# MotorCell.net
KiCad netlist of a schematic drawn in Altium Designer
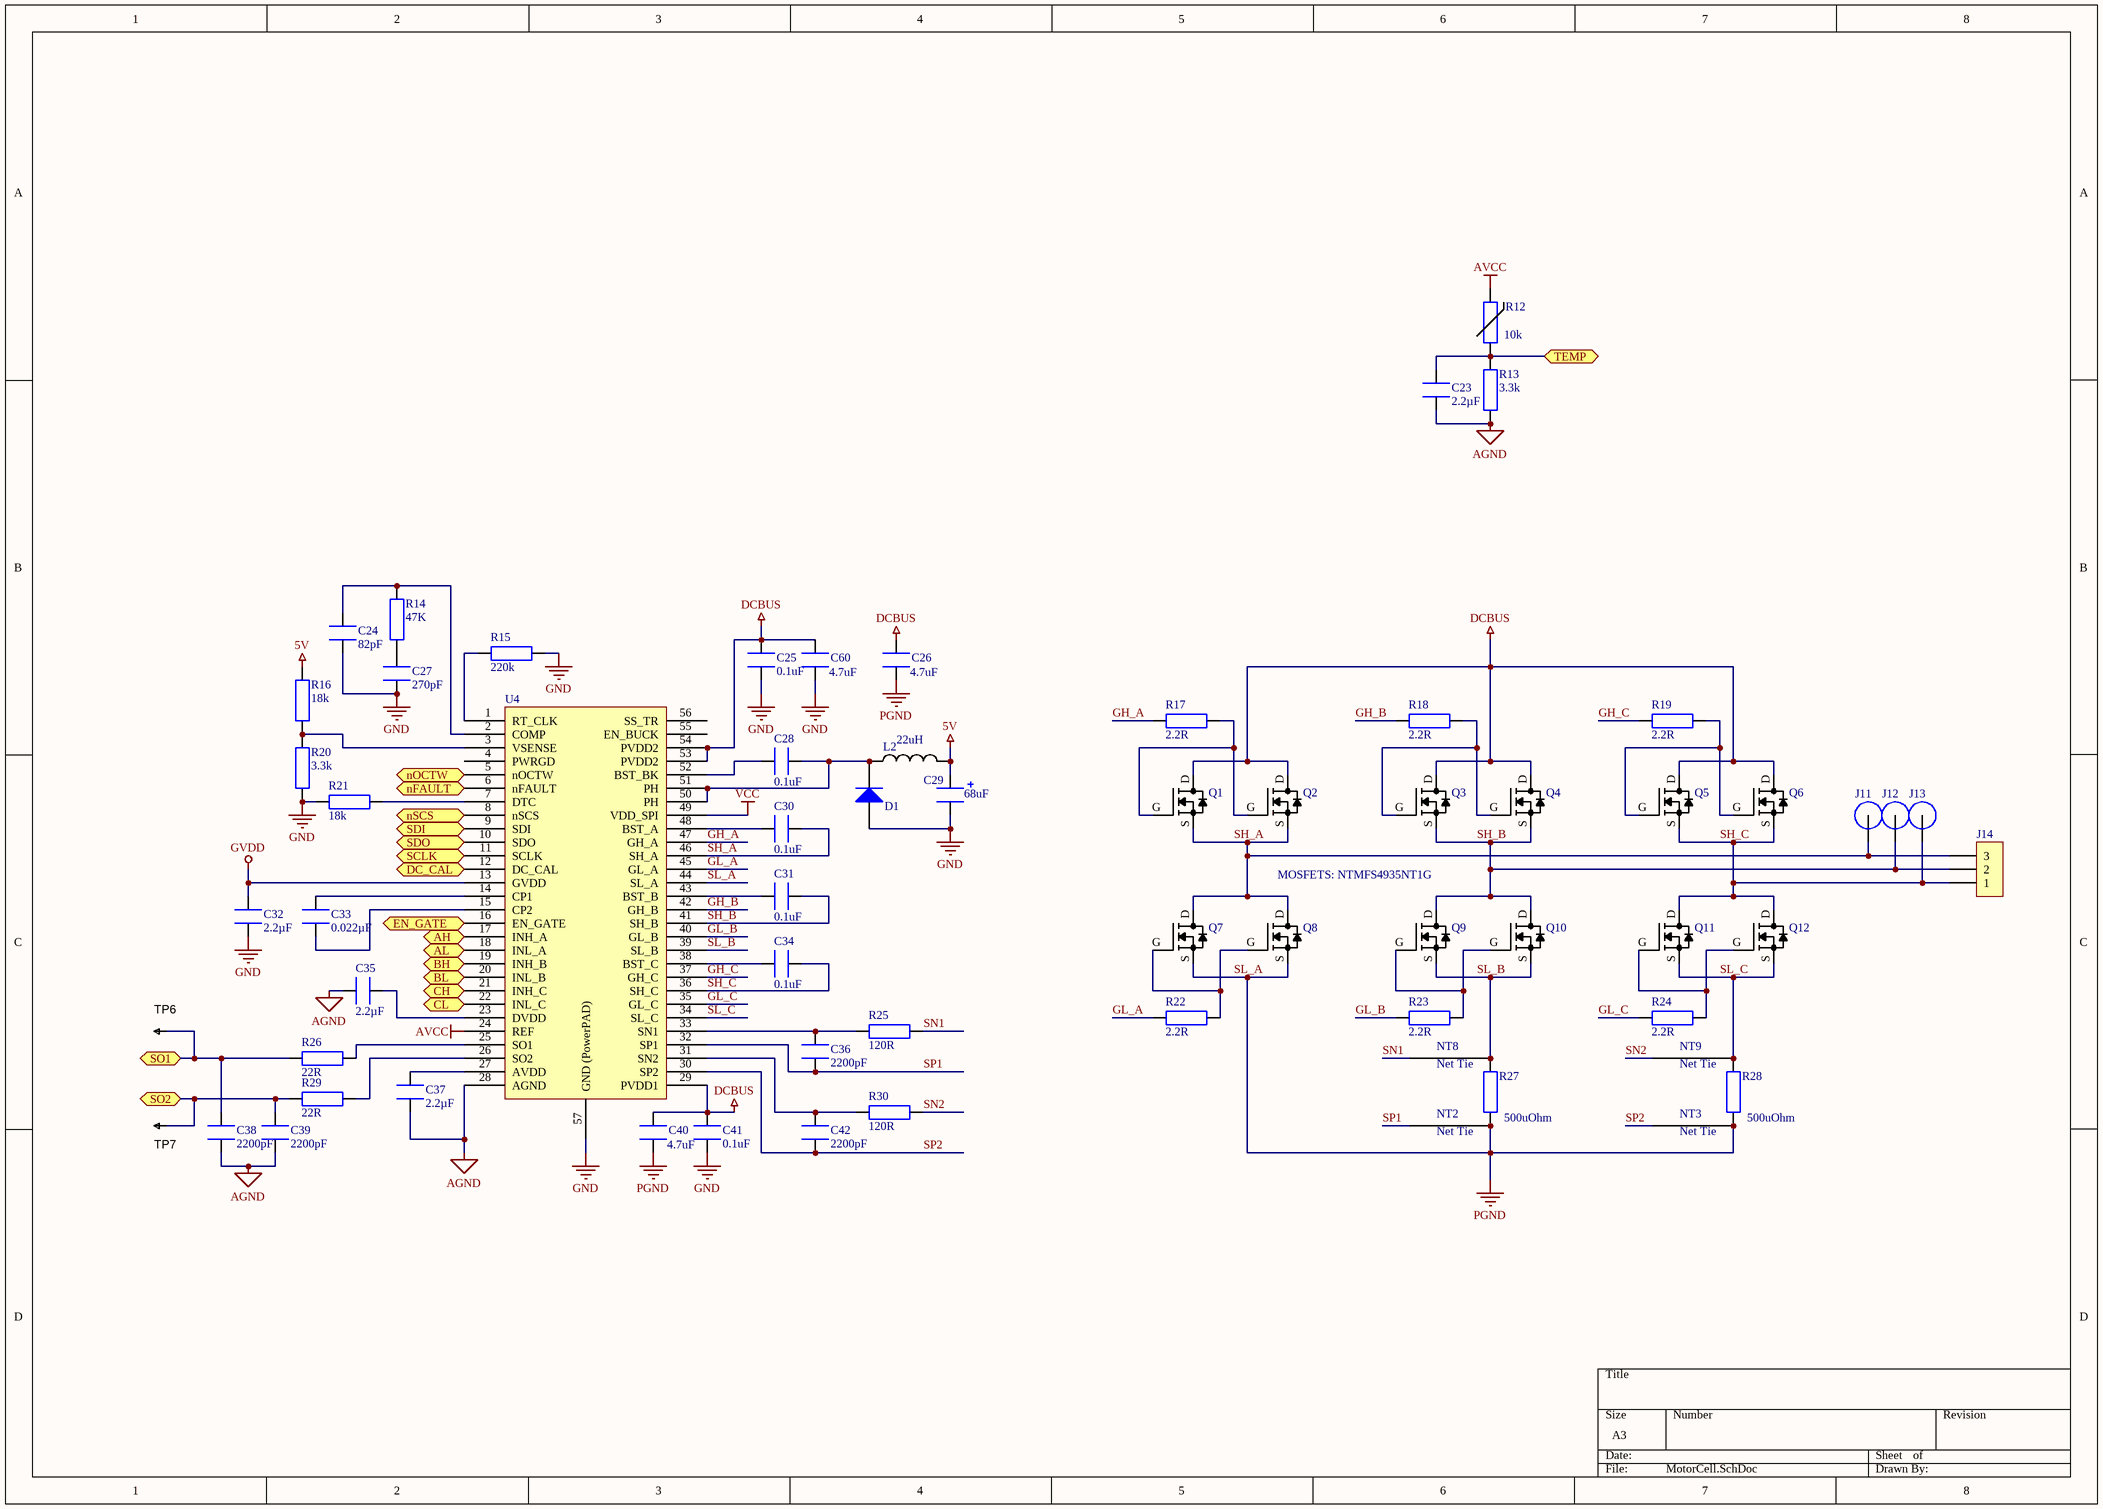
[diagram p0: MotorCell.SchDoc]

(export (version "E")
  (design (tool "Eeschema 10.0.6"))
  (components
    (comp (ref "C23")
      (value "2.2µF")
      (footprint "CAPC1608X09L")
      (description "CAP CER 2.2UF 16V X5R 0603")
      (fields
        (field (name "MANUFACTURER") "Murata Electronics North America")
        (field (name "MANUFACTURER PART NUMBER") "GRM188R61C225KE15D")
      )
      (libsource (lib "CustomComponents") (part "GRM188R61C225KE15D"))
    )
    (comp (ref "C24")
      (value "82pF")
      (footprint "CAPC1608X09L")
      (description "CAP CER 82PF 100V NP0 0603")
      (fields
        (field (name "MANUFACTURER") "Murata Electronics North America")
        (field (name "MANUFACTURER PART NUMBER") "GRM1885C2A820JA01D")
      )
      (libsource (lib "CustomComponents") (part "GRM1885C2A820JA01D"))
    )
    (comp (ref "C25")
      (value "0.1uF")
      (footprint "CAPC1608X09L")
      (description "CAP CER 0.1UF 50V X7R 0603")
      (fields
        (field (name "MANUFACTURER") "Murata Electronics North America")
        (field (name "MANUFACTURER PART NUMBER") "GRM188R71H104KA93D")
      )
      (libsource (lib "CustomComponents") (part "GRM188R71H104KA93D"))
    )
    (comp (ref "C26")
      (value "4.7uF")
      (footprint "CAPC2012X09N")
      (description "CAP CER 4.7UF 35V X5R 0805")
      (fields
        (field (name "MANUFACTURER") "Murata Electronics North America")
        (field (name "TOLERANCE") "±10%")
      )
      (libsource (lib "CustomComponents") (part "GRM219R6YA475KA73D"))
    )
    (comp (ref "C27")
      (value "270pF")
      (footprint "CAPC1608X09L")
      (description "CAP CER 270PF 50V NP0 0603")
      (fields
        (field (name "MANUFACTURER") "Murata Electronics North America")
        (field (name "MANUFACTURER PART NUMBER") "GRM1885C1H271JA01D")
      )
      (libsource (lib "CustomComponents") (part "GRM1885C1H271JA01D"))
    )
    (comp (ref "C28")
      (value "0.1uF")
      (footprint "CAPC1608X09L")
      (description "CAP CER 0.1UF 50V X7R 0603")
      (fields
        (field (name "MANUFACTURER") "Murata Electronics North America")
        (field (name "MANUFACTURER PART NUMBER") "GRM188R71H104KA93D")
      )
      (libsource (lib "CustomComponents") (part "GRM188R71H104KA93D"))
    )
    (comp (ref "C29")
      (value "68uF")
      (footprint "CAPCP6032X28N")
      (description "CAP TANT 68UF 16V 20% 2312 250mOhm")
      (fields (field (name "MANUFACTURER") "KEMET") (field (name "TOLERANCE") "±20%"))
      (libsource (lib "CustomComponents") (part "T495C686M016ATE250"))
    )
    (comp (ref "C30")
      (value "0.1uF")
      (footprint "CAPC1608X09L")
      (description "CAP CER 0.1UF 50V X7R 0603")
      (fields
        (field (name "MANUFACTURER") "Murata Electronics North America")
        (field (name "MANUFACTURER PART NUMBER") "GRM188R71H104KA93D")
      )
      (libsource (lib "CustomComponents") (part "GRM188R71H104KA93D"))
    )
    (comp (ref "C31")
      (value "0.1uF")
      (footprint "CAPC1608X09L")
      (description "CAP CER 0.1UF 50V X7R 0603")
      (fields
        (field (name "MANUFACTURER") "Murata Electronics North America")
        (field (name "MANUFACTURER PART NUMBER") "GRM188R71H104KA93D")
      )
      (libsource (lib "CustomComponents") (part "GRM188R71H104KA93D"))
    )
    (comp (ref "C32")
      (value "2.2µF")
      (footprint "CAPC1608X09L")
      (description "CAP CER 2.2UF 16V X5R 0603")
      (fields
        (field (name "MANUFACTURER") "Murata Electronics North America")
        (field (name "MANUFACTURER PART NUMBER") "GRM188R61C225KE15D")
      )
      (libsource (lib "CustomComponents") (part "GRM188R61C225KE15D"))
    )
    (comp (ref "C33")
      (value "0.022µF")
      (footprint "CAPC1608X09L")
      (description "CAP CER 0.022UF 50V X7R 0603")
      (fields
        (field (name "MANUFACTURER") "Murata Electronics North America")
        (field (name "MANUFACTURER PART NUMBER") "GRM188R71H223KA01D")
      )
      (libsource (lib "CustomComponents") (part "GRM188R71H223KA01D"))
    )
    (comp (ref "C34")
      (value "0.1uF")
      (footprint "CAPC1608X09L")
      (description "CAP CER 0.1UF 50V X7R 0603")
      (fields
        (field (name "MANUFACTURER") "Murata Electronics North America")
        (field (name "MANUFACTURER PART NUMBER") "GRM188R71H104KA93D")
      )
      (libsource (lib "CustomComponents") (part "GRM188R71H104KA93D"))
    )
    (comp (ref "C35")
      (value "2.2µF")
      (footprint "CAPC1608X09L")
      (description "CAP CER 2.2UF 16V X5R 0603")
      (fields
        (field (name "MANUFACTURER") "Murata Electronics North America")
        (field (name "MANUFACTURER PART NUMBER") "GRM188R61C225KE15D")
      )
      (libsource (lib "CustomComponents") (part "GRM188R61C225KE15D"))
    )
    (comp (ref "C36")
      (value "2200pF")
      (footprint "CAPC1608X09L")
      (description "CAP CER 2200PF 50V NP0 0603")
      (fields
        (field (name "MANUFACTURER") "Murata Electronics North America")
        (field (name "TOLERANCE") "±5%")
      )
      (libsource (lib "CustomComponents") (part "GRM1885C1H222JA01D"))
    )
    (comp (ref "C37")
      (value "2.2µF")
      (footprint "CAPC1608X09L")
      (description "CAP CER 2.2UF 16V X5R 0603")
      (fields
        (field (name "MANUFACTURER") "Murata Electronics North America")
        (field (name "MANUFACTURER PART NUMBER") "GRM188R61C225KE15D")
      )
      (libsource (lib "CustomComponents") (part "GRM188R61C225KE15D"))
    )
    (comp (ref "C38")
      (value "2200pF")
      (footprint "CAPC1608X09L")
      (description "CAP CER 2200PF 50V NP0 0603")
      (fields
        (field (name "MANUFACTURER") "Murata Electronics North America")
        (field (name "TOLERANCE") "±5%")
      )
      (libsource (lib "CustomComponents") (part "GRM1885C1H222JA01D"))
    )
    (comp (ref "C39")
      (value "2200pF")
      (footprint "CAPC1608X09L")
      (description "CAP CER 2200PF 50V NP0 0603")
      (fields
        (field (name "MANUFACTURER") "Murata Electronics North America")
        (field (name "TOLERANCE") "±5%")
      )
      (libsource (lib "CustomComponents") (part "GRM1885C1H222JA01D"))
    )
    (comp (ref "C40")
      (value "4.7uF")
      (footprint "CAPC2012X09N")
      (description "CAP CER 4.7UF 35V X5R 0805")
      (fields
        (field (name "MANUFACTURER") "Murata Electronics North America")
        (field (name "TOLERANCE") "±10%")
      )
      (libsource (lib "CustomComponents") (part "GRM219R6YA475KA73D"))
    )
    (comp (ref "C41")
      (value "0.1uF")
      (footprint "CAPC1608X09L")
      (description "CAP CER 0.1UF 50V X7R 0603")
      (fields
        (field (name "MANUFACTURER") "Murata Electronics North America")
        (field (name "MANUFACTURER PART NUMBER") "GRM188R71H104KA93D")
      )
      (libsource (lib "CustomComponents") (part "GRM188R71H104KA93D"))
    )
    (comp (ref "C42")
      (value "2200pF")
      (footprint "CAPC1608X09L")
      (description "CAP CER 2200PF 50V NP0 0603")
      (fields
        (field (name "MANUFACTURER") "Murata Electronics North America")
        (field (name "TOLERANCE") "±5%")
      )
      (libsource (lib "CustomComponents") (part "GRM1885C1H222JA01D"))
    )
    (comp (ref "C60")
      (value "4.7uF")
      (footprint "CAPC2012X09N")
      (description "CAP CER 4.7UF 35V X5R 0805")
      (fields
        (field (name "MANUFACTURER") "Murata Electronics North America")
        (field (name "TOLERANCE") "±10%")
      )
      (libsource (lib "CustomComponents") (part "GRM219R6YA475KA73D"))
    )
    (comp (ref "D1")
      (value "~")
      (footprint "DIOM2717X10N")
      (description "Rectifier Diode, Single, 40 V, 1 A, SOD-123FL, 2, 550 mV")
      (libsource (lib "CustomComponents") (part "MBR140SFT1G"))
    )
    (comp (ref "J11")
      (value "~")
      (footprint "M3 Spade Hole")
      (description "M3 Spade Terminal")
      (libsource (lib "CustomComponents") (part "M3 Spade Terminal"))
    )
    (comp (ref "J12")
      (value "~")
      (footprint "M3 Spade Hole")
      (description "M3 Spade Terminal")
      (libsource (lib "CustomComponents") (part "M3 Spade Terminal"))
    )
    (comp (ref "J13")
      (value "~")
      (footprint "M3 Spade Hole")
      (description "M3 Spade Terminal")
      (libsource (lib "CustomComponents") (part "M3 Spade Terminal"))
    )
    (comp (ref "J14")
      (value "1704936")
      (footprint "1704936")
      (description "CONN TERM BLOCK 3POS 7.62MM")
      (fields (field (name "MANUFACTURER") "Phoenix Contact") (field (name "VOLTAGE") "300V"))
      (libsource (lib "CustomComponents") (part "1704936"))
    )
    (comp (ref "L2")
      (value "22uH")
      (footprint "INDC6060X28N")
      (description "INDUCTOR 22UH 1.4A 175.5 MOHM")
      (libsource (lib "CustomComponents") (part "NR6028T220M"))
    )
    (comp (ref "NT2")
      (value "0.25mm")
      (footprint "NetTie_0.25mm")
      (libsource (lib "CustomComponents") (part "NetTie_0.25mm"))
    )
    (comp (ref "NT3")
      (value "0.25mm")
      (footprint "NetTie_0.25mm")
      (libsource (lib "CustomComponents") (part "NetTie_0.25mm"))
    )
    (comp (ref "NT8")
      (value "0.25mm")
      (footprint "NetTie_0.25mm")
      (libsource (lib "CustomComponents") (part "NetTie_0.25mm"))
    )
    (comp (ref "NT9")
      (value "0.25mm")
      (footprint "NetTie_0.25mm")
      (libsource (lib "CustomComponents") (part "NetTie_0.25mm"))
    )
    (comp (ref "Q1")
      (value "~")
      (footprint "SO8FL")
      (description "MOSFET N-CH 30V 13A SO8FL")
      (fields
        (field (name "MANUFACTURER") "ON Semiconductor")
        (field (name "MANUFACTURER PART NUMBER") "NTMFS4935NT1G")
      )
      (libsource (lib "CustomComponents") (part "NTMFS4935NT1G"))
    )
    (comp (ref "Q2")
      (value "FILL_FOOTPRINT")
      (footprint "SO8FL_FILL")
      (description "MOSFET N-CH 30V 13A SO8FL")
      (fields
        (field (name "MANUFACTURER") "ON Semiconductor")
        (field (name "MANUFACTURER PART NUMBER") "NTMFS4935NT1G")
      )
      (libsource (lib "CustomComponents") (part "NTMFS4935NT1G"))
    )
    (comp (ref "Q3")
      (value "~")
      (footprint "SO8FL")
      (description "MOSFET N-CH 30V 13A SO8FL")
      (fields
        (field (name "MANUFACTURER") "ON Semiconductor")
        (field (name "MANUFACTURER PART NUMBER") "NTMFS4935NT1G")
      )
      (libsource (lib "CustomComponents") (part "NTMFS4935NT1G"))
    )
    (comp (ref "Q4")
      (value "FILL_FOOTPRINT")
      (footprint "SO8FL_FILL")
      (description "MOSFET N-CH 30V 13A SO8FL")
      (fields
        (field (name "MANUFACTURER") "ON Semiconductor")
        (field (name "MANUFACTURER PART NUMBER") "NTMFS4935NT1G")
      )
      (libsource (lib "CustomComponents") (part "NTMFS4935NT1G"))
    )
    (comp (ref "Q5")
      (value "~")
      (footprint "SO8FL")
      (description "MOSFET N-CH 30V 13A SO8FL")
      (fields
        (field (name "MANUFACTURER") "ON Semiconductor")
        (field (name "MANUFACTURER PART NUMBER") "NTMFS4935NT1G")
      )
      (libsource (lib "CustomComponents") (part "NTMFS4935NT1G"))
    )
    (comp (ref "Q6")
      (value "FILL_FOOTPRINT")
      (footprint "SO8FL_FILL")
      (description "MOSFET N-CH 30V 13A SO8FL")
      (fields
        (field (name "MANUFACTURER") "ON Semiconductor")
        (field (name "MANUFACTURER PART NUMBER") "NTMFS4935NT1G")
      )
      (libsource (lib "CustomComponents") (part "NTMFS4935NT1G"))
    )
    (comp (ref "Q7")
      (value "~")
      (footprint "SO8FL")
      (description "MOSFET N-CH 30V 13A SO8FL")
      (fields
        (field (name "MANUFACTURER") "ON Semiconductor")
        (field (name "MANUFACTURER PART NUMBER") "NTMFS4935NT1G")
      )
      (libsource (lib "CustomComponents") (part "NTMFS4935NT1G"))
    )
    (comp (ref "Q8")
      (value "~")
      (footprint "SO8FL")
      (description "MOSFET N-CH 30V 13A SO8FL")
      (fields
        (field (name "MANUFACTURER") "ON Semiconductor")
        (field (name "MANUFACTURER PART NUMBER") "NTMFS4935NT1G")
      )
      (libsource (lib "CustomComponents") (part "NTMFS4935NT1G"))
    )
    (comp (ref "Q9")
      (value "~")
      (footprint "SO8FL")
      (description "MOSFET N-CH 30V 13A SO8FL")
      (fields
        (field (name "MANUFACTURER") "ON Semiconductor")
        (field (name "MANUFACTURER PART NUMBER") "NTMFS4935NT1G")
      )
      (libsource (lib "CustomComponents") (part "NTMFS4935NT1G"))
    )
    (comp (ref "Q10")
      (value "~")
      (footprint "SO8FL")
      (description "MOSFET N-CH 30V 13A SO8FL")
      (fields
        (field (name "MANUFACTURER") "ON Semiconductor")
        (field (name "MANUFACTURER PART NUMBER") "NTMFS4935NT1G")
      )
      (libsource (lib "CustomComponents") (part "NTMFS4935NT1G"))
    )
    (comp (ref "Q11")
      (value "~")
      (footprint "SO8FL")
      (description "MOSFET N-CH 30V 13A SO8FL")
      (fields
        (field (name "MANUFACTURER") "ON Semiconductor")
        (field (name "MANUFACTURER PART NUMBER") "NTMFS4935NT1G")
      )
      (libsource (lib "CustomComponents") (part "NTMFS4935NT1G"))
    )
    (comp (ref "Q12")
      (value "~")
      (footprint "SO8FL")
      (description "MOSFET N-CH 30V 13A SO8FL")
      (fields
        (field (name "MANUFACTURER") "ON Semiconductor")
        (field (name "MANUFACTURER PART NUMBER") "NTMFS4935NT1G")
      )
      (libsource (lib "CustomComponents") (part "NTMFS4935NT1G"))
    )
    (comp (ref "R12")
      (value "10k")
      (footprint "RESC1005X40N")
      (description "THERMISTOR 10K OHM NTC 0402 SMD")
      (libsource (lib "CustomComponents") (part "NCP15XH103F03RC"))
    )
    (comp (ref "R13")
      (value "3.3k")
      (footprint "RESC1608X55N")
      (description "RES SMD 3.3K OHM 1% 1/10W 0603")
      (fields
        (field (name "MANUFACTURER") "Yageo")
        (field (name "MANUFACTURER PART NUMBER") "RC0603FR-073K3L")
      )
      (libsource (lib "CustomComponents") (part "RC0603FR-073K3L"))
    )
    (comp (ref "R14")
      (value "47K")
      (footprint "RESC1608X55N")
      (description "RES SMD 47K OHM 1% 1/10W 0603")
      (fields
        (field (name "MANUFACTURER") "Yageo")
        (field (name "MANUFACTURER PART NUMBER") "RC0603FR-0747KL")
      )
      (libsource (lib "CustomComponents") (part "RC0603FR-0747KL"))
    )
    (comp (ref "R15")
      (value "220k")
      (footprint "RESC1608X55N")
      (description "RES SMD 220K OHM 1% 1/10W 0603")
      (fields
        (field (name "MANUFACTURER") "Yageo")
        (field (name "MANUFACTURER PART NUMBER") "RC0603FR-07220KL")
      )
      (libsource (lib "CustomComponents") (part "RC0603FR-07220KL"))
    )
    (comp (ref "R16")
      (value "18k")
      (footprint "RESC1608X55N")
      (description "RES SMD 18K OHM 1% 1/10W 0603")
      (fields
        (field (name "MANUFACTURER") "Yageo")
        (field (name "MANUFACTURER PART NUMBER") "RC0603FR-0718KL")
      )
      (libsource (lib "CustomComponents") (part "RC0603FR-0718KL"))
    )
    (comp (ref "R17")
      (value "2.2R")
      (footprint "RESC1608X55N")
      (description "RES SMD 2.2 OHM 1% 1/10W 0603")
      (fields
        (field (name "MANUFACTURER") "Yageo")
        (field (name "MANUFACTURER PART NUMBER") "RC0603FR-072R2L")
      )
      (libsource (lib "CustomComponents") (part "RC0603FR-072R2L"))
    )
    (comp (ref "R18")
      (value "2.2R")
      (footprint "RESC1608X55N")
      (description "RES SMD 2.2 OHM 1% 1/10W 0603")
      (fields
        (field (name "MANUFACTURER") "Yageo")
        (field (name "MANUFACTURER PART NUMBER") "RC0603FR-072R2L")
      )
      (libsource (lib "CustomComponents") (part "RC0603FR-072R2L"))
    )
    (comp (ref "R19")
      (value "2.2R")
      (footprint "RESC1608X55N")
      (description "RES SMD 2.2 OHM 1% 1/10W 0603")
      (fields
        (field (name "MANUFACTURER") "Yageo")
        (field (name "MANUFACTURER PART NUMBER") "RC0603FR-072R2L")
      )
      (libsource (lib "CustomComponents") (part "RC0603FR-072R2L"))
    )
    (comp (ref "R20")
      (value "3.3k")
      (footprint "RESC1608X55N")
      (description "RES SMD 3.3K OHM 1% 1/10W 0603")
      (fields
        (field (name "MANUFACTURER") "Yageo")
        (field (name "MANUFACTURER PART NUMBER") "RC0603FR-073K3L")
      )
      (libsource (lib "CustomComponents") (part "RC0603FR-073K3L"))
    )
    (comp (ref "R21")
      (value "18k")
      (footprint "RESC1608X55N")
      (description "RES SMD 18K OHM 1% 1/10W 0603")
      (fields
        (field (name "MANUFACTURER") "Yageo")
        (field (name "MANUFACTURER PART NUMBER") "RC0603FR-0718KL")
      )
      (libsource (lib "CustomComponents") (part "RC0603FR-0718KL"))
    )
    (comp (ref "R22")
      (value "2.2R")
      (footprint "RESC1608X55N")
      (description "RES SMD 2.2 OHM 1% 1/10W 0603")
      (fields
        (field (name "MANUFACTURER") "Yageo")
        (field (name "MANUFACTURER PART NUMBER") "RC0603FR-072R2L")
      )
      (libsource (lib "CustomComponents") (part "RC0603FR-072R2L"))
    )
    (comp (ref "R23")
      (value "2.2R")
      (footprint "RESC1608X55N")
      (description "RES SMD 2.2 OHM 1% 1/10W 0603")
      (fields
        (field (name "MANUFACTURER") "Yageo")
        (field (name "MANUFACTURER PART NUMBER") "RC0603FR-072R2L")
      )
      (libsource (lib "CustomComponents") (part "RC0603FR-072R2L"))
    )
    (comp (ref "R24")
      (value "2.2R")
      (footprint "RESC1608X55N")
      (description "RES SMD 2.2 OHM 1% 1/10W 0603")
      (fields
        (field (name "MANUFACTURER") "Yageo")
        (field (name "MANUFACTURER PART NUMBER") "RC0603FR-072R2L")
      )
      (libsource (lib "CustomComponents") (part "RC0603FR-072R2L"))
    )
    (comp (ref "R25")
      (value "120R")
      (footprint "RESC1608X55N")
      (description "RES SMD 120 OHM 1% 1/10W 0603")
      (fields
        (field (name "MANUFACTURER") "Yageo")
        (field (name "MANUFACTURER PART NUMBER") "RC0603FR-07120RL")
      )
      (libsource (lib "CustomComponents") (part "RC0603FR-07120RL"))
    )
    (comp (ref "R26")
      (value "22R")
      (footprint "RESC1608X55N")
      (description "RES SMD 22 OHM 1% 1/10W 0603")
      (fields
        (field (name "MANUFACTURER") "Yageo")
        (field (name "MANUFACTURER PART NUMBER") "RC0603FR-0722RL")
      )
      (libsource (lib "CustomComponents") (part "RC0603FR-0722RL"))
    )
    (comp (ref "R27")
      (value "500uOhm")
      (footprint "RESC6432X09N")
      (description "RES SMD 0.0005 OHM 1% 3W 2512")
      (fields (field (name "MANUFACTURER") "Riedon") (field (name "TOLERANCE") "±1%"))
      (libsource (lib "CustomComponents") (part "CSR2512C0R0005F"))
    )
    (comp (ref "R28")
      (value "500uOhm")
      (footprint "RESC6432X09N")
      (description "RES SMD 0.0005 OHM 1% 3W 2512")
      (fields (field (name "MANUFACTURER") "Riedon") (field (name "TOLERANCE") "±1%"))
      (libsource (lib "CustomComponents") (part "CSR2512C0R0005F"))
    )
    (comp (ref "R29")
      (value "22R")
      (footprint "RESC1608X55N")
      (description "RES SMD 22 OHM 1% 1/10W 0603")
      (fields
        (field (name "MANUFACTURER") "Yageo")
        (field (name "MANUFACTURER PART NUMBER") "RC0603FR-0722RL")
      )
      (libsource (lib "CustomComponents") (part "RC0603FR-0722RL"))
    )
    (comp (ref "R30")
      (value "120R")
      (footprint "RESC1608X55N")
      (description "RES SMD 120 OHM 1% 1/10W 0603")
      (fields
        (field (name "MANUFACTURER") "Yageo")
        (field (name "MANUFACTURER PART NUMBER") "RC0603FR-07120RL")
      )
      (libsource (lib "CustomComponents") (part "RC0603FR-07120RL"))
    )
    (comp (ref "TP6")
      (value "TESTPOINT")
      (footprint "TP-R30")
      (description "SMD test pin")
      (libsource (lib "PBL - Test Points") (part "TESTPOINT"))
    )
    (comp (ref "TP7")
      (value "TESTPOINT")
      (footprint "TP-R30")
      (description "SMD test pin")
      (libsource (lib "PBL - Test Points") (part "TESTPOINT"))
    )
    (comp (ref "U4")
      (value "~")
      (footprint "TSSOP50P810X120_HS-57N")
      (description "MOTOR DRIVER, 3PH, 56HTSSOP")
      (libsource (lib "CustomComponents") (part "DRV8301"))
    )
  )
  (nets
    (net (code "1") (name "/AH") (class "Default")
      (node (ref "U4") (pin "17") (pinfunction "INH_A_17") (pintype "passive"))
    )
    (net (code "2") (name "/AL") (class "Default")
      (node (ref "U4") (pin "18") (pinfunction "INL_A_18") (pintype "passive"))
    )
    (net (code "3") (name "/BH") (class "Default")
      (node (ref "U4") (pin "19") (pinfunction "INH_B_19") (pintype "passive"))
    )
    (net (code "4") (name "/BL") (class "Default")
      (node (ref "U4") (pin "20") (pinfunction "INL_B_20") (pintype "passive"))
    )
    (net (code "5") (name "/CH") (class "Default")
      (node (ref "U4") (pin "21") (pinfunction "INH_C_21") (pintype "passive"))
    )
    (net (code "6") (name "/CL") (class "Default")
      (node (ref "U4") (pin "22") (pinfunction "INL_C_22") (pintype "passive"))
    )
    (net (code "7") (name "/DC_CAL") (class "Default")
      (node (ref "U4") (pin "12") (pinfunction "DC_CAL_12") (pintype "passive"))
    )
    (net (code "8") (name "/EN_GATE") (class "Default")
      (node (ref "U4") (pin "16") (pinfunction "EN_GATE_16") (pintype "passive"))
    )
    (net (code "9") (name "/GH_A") (class "Default")
      (node (ref "R17") (pin "2") (pinfunction "0_2") (pintype "passive"))
      (node (ref "U4") (pin "47") (pinfunction "GH_A_47") (pintype "passive"))
    )
    (net (code "10") (name "/GH_B") (class "Default")
      (node (ref "R18") (pin "2") (pinfunction "0_2") (pintype "passive"))
      (node (ref "U4") (pin "42") (pinfunction "GH_B_42") (pintype "passive"))
    )
    (net (code "11") (name "/GH_C") (class "Default")
      (node (ref "R19") (pin "2") (pinfunction "0_2") (pintype "passive"))
      (node (ref "U4") (pin "37") (pinfunction "GH_C_37") (pintype "passive"))
    )
    (net (code "12") (name "/GL_A") (class "Default")
      (node (ref "R22") (pin "2") (pinfunction "0_2") (pintype "passive"))
      (node (ref "U4") (pin "45") (pinfunction "GL_A_45") (pintype "passive"))
    )
    (net (code "13") (name "/GL_B") (class "Default")
      (node (ref "R23") (pin "2") (pinfunction "0_2") (pintype "passive"))
      (node (ref "U4") (pin "40") (pinfunction "GL_B_40") (pintype "passive"))
    )
    (net (code "14") (name "/GL_C") (class "Default")
      (node (ref "R24") (pin "2") (pinfunction "0_2") (pintype "passive"))
      (node (ref "U4") (pin "35") (pinfunction "GL_C_35") (pintype "passive"))
    )
    (net (code "15") (name "/SCLK") (class "Default")
      (node (ref "U4") (pin "11") (pinfunction "SCLK_11") (pintype "passive"))
    )
    (net (code "16") (name "/SDI") (class "Default")
      (node (ref "U4") (pin "9") (pinfunction "SDI_9") (pintype "passive"))
    )
    (net (code "17") (name "/SDO") (class "Default")
      (node (ref "U4") (pin "10") (pinfunction "SDO_10") (pintype "passive"))
    )
    (net (code "18") (name "/SH_A") (class "Default")
      (node (ref "C30") (pin "1") (pinfunction "1_1") (pintype "passive"))
      (node (ref "J11") (pin "1") (pinfunction "1_1") (pintype "passive"))
      (node (ref "J14") (pin "3") (pinfunction "3_3") (pintype "passive"))
      (node (ref "Q1") (pin "S") (pinfunction "S_S") (pintype "passive"))
      (node (ref "Q2") (pin "S") (pinfunction "S_S") (pintype "passive"))
      (node (ref "Q7") (pin "D") (pinfunction "D_D") (pintype "passive"))
      (node (ref "Q8") (pin "D") (pinfunction "D_D") (pintype "passive"))
      (node (ref "U4") (pin "46") (pinfunction "SH_A_46") (pintype "passive"))
    )
    (net (code "19") (name "/SH_B") (class "Default")
      (node (ref "C31") (pin "1") (pinfunction "1_1") (pintype "passive"))
      (node (ref "J12") (pin "1") (pinfunction "1_1") (pintype "passive"))
      (node (ref "J14") (pin "2") (pinfunction "2_2") (pintype "passive"))
      (node (ref "Q10") (pin "D") (pinfunction "D_D") (pintype "passive"))
      (node (ref "Q3") (pin "S") (pinfunction "S_S") (pintype "passive"))
      (node (ref "Q4") (pin "S") (pinfunction "S_S") (pintype "passive"))
      (node (ref "Q9") (pin "D") (pinfunction "D_D") (pintype "passive"))
      (node (ref "U4") (pin "41") (pinfunction "SH_B_41") (pintype "passive"))
    )
    (net (code "20") (name "/SH_C") (class "Default")
      (node (ref "C34") (pin "1") (pinfunction "1_1") (pintype "passive"))
      (node (ref "J13") (pin "1") (pinfunction "1_1") (pintype "passive"))
      (node (ref "J14") (pin "1") (pinfunction "1_1") (pintype "passive"))
      (node (ref "Q11") (pin "D") (pinfunction "D_D") (pintype "passive"))
      (node (ref "Q12") (pin "D") (pinfunction "D_D") (pintype "passive"))
      (node (ref "Q5") (pin "S") (pinfunction "S_S") (pintype "passive"))
      (node (ref "Q6") (pin "S") (pinfunction "S_S") (pintype "passive"))
      (node (ref "U4") (pin "36") (pinfunction "SH_C_36") (pintype "passive"))
    )
    (net (code "21") (name "/SL_B") (class "Default")
      (node (ref "NT8") (pin "2") (pintype "passive"))
      (node (ref "Q10") (pin "S") (pinfunction "S_S") (pintype "passive"))
      (node (ref "Q9") (pin "S") (pinfunction "S_S") (pintype "passive"))
      (node (ref "R27") (pin "2") (pinfunction "0_2") (pintype "passive"))
      (node (ref "U4") (pin "39") (pinfunction "SL_B_39") (pintype "passive"))
    )
    (net (code "22") (name "/SL_C") (class "Default")
      (node (ref "NT9") (pin "2") (pintype "passive"))
      (node (ref "Q11") (pin "S") (pinfunction "S_S") (pintype "passive"))
      (node (ref "Q12") (pin "S") (pinfunction "S_S") (pintype "passive"))
      (node (ref "R28") (pin "2") (pinfunction "0_2") (pintype "passive"))
      (node (ref "U4") (pin "34") (pinfunction "SL_C_34") (pintype "passive"))
    )
    (net (code "23") (name "/SN1") (class "Default")
      (node (ref "NT8") (pin "1") (pintype "passive"))
      (node (ref "R25") (pin "1") (pinfunction "0_1") (pintype "passive"))
    )
    (net (code "24") (name "/SN2") (class "Default")
      (node (ref "NT9") (pin "1") (pintype "passive"))
      (node (ref "R30") (pin "1") (pinfunction "0_1") (pintype "passive"))
    )
    (net (code "25") (name "/SO1") (class "Default")
      (node (ref "C38") (pin "1") (pinfunction "1_1") (pintype "passive"))
      (node (ref "R26") (pin "2") (pinfunction "0_2") (pintype "passive"))
      (node (ref "TP6") (pin "1") (pintype "passive"))
    )
    (net (code "26") (name "/SO2") (class "Default")
      (node (ref "C39") (pin "1") (pinfunction "1_1") (pintype "passive"))
      (node (ref "R29") (pin "2") (pinfunction "0_2") (pintype "passive"))
      (node (ref "TP7") (pin "1") (pintype "passive"))
    )
    (net (code "27") (name "/SP1") (class "Default")
      (node (ref "C36") (pin "2") (pinfunction "2_2") (pintype "passive"))
      (node (ref "NT2") (pin "1") (pintype "passive"))
      (node (ref "U4") (pin "32") (pinfunction "SP1_32") (pintype "passive"))
    )
    (net (code "28") (name "/SP2") (class "Default")
      (node (ref "C42") (pin "2") (pinfunction "2_2") (pintype "passive"))
      (node (ref "NT3") (pin "1") (pintype "passive"))
      (node (ref "U4") (pin "30") (pinfunction "SP2_30") (pintype "passive"))
    )
    (net (code "29") (name "/TEMP") (class "Default")
      (node (ref "C23") (pin "2") (pinfunction "2_2") (pintype "passive"))
      (node (ref "R12") (pin "1") (pinfunction "0_1") (pintype "passive"))
      (node (ref "R13") (pin "1") (pinfunction "0_1") (pintype "passive"))
    )
    (net (code "30") (name "/nFAULT") (class "Default")
      (node (ref "U4") (pin "6") (pinfunction "nFAULT_6") (pintype "passive"))
    )
    (net (code "31") (name "/nOCTW") (class "Default")
      (node (ref "U4") (pin "5") (pinfunction "nOCTW_5") (pintype "passive"))
    )
    (net (code "32") (name "/nSCS") (class "Default")
      (node (ref "U4") (pin "8") (pinfunction "nSCS_8") (pintype "passive"))
    )
    (net (code "33") (name "5V") (class "Default")
      (node (ref "C29") (pin "1") (pinfunction "1_1") (pintype "passive"))
      (node (ref "L2") (pin "2") (pinfunction "2_2") (pintype "passive"))
      (node (ref "R16") (pin "1") (pinfunction "0_1") (pintype "passive"))
    )
    (net (code "34") (name "AGND") (class "Default")
      (node (ref "C23") (pin "1") (pinfunction "1_1") (pintype "passive"))
      (node (ref "C35") (pin "1") (pinfunction "1_1") (pintype "passive"))
      (node (ref "C37") (pin "1") (pinfunction "1_1") (pintype "passive"))
      (node (ref "C38") (pin "2") (pinfunction "2_2") (pintype "passive"))
      (node (ref "C39") (pin "2") (pinfunction "2_2") (pintype "passive"))
      (node (ref "R13") (pin "2") (pinfunction "0_2") (pintype "passive"))
      (node (ref "U4") (pin "28") (pinfunction "AGND_28") (pintype "passive"))
    )
    (net (code "35") (name "AVCC") (class "Default")
      (node (ref "R12") (pin "2") (pinfunction "0_2") (pintype "passive"))
      (node (ref "U4") (pin "24") (pinfunction "REF_24") (pintype "passive"))
    )
    (net (code "36") (name "DCBUS") (class "Default")
      (node (ref "C25") (pin "1") (pinfunction "1_1") (pintype "passive"))
      (node (ref "C26") (pin "2") (pinfunction "2_2") (pintype "passive"))
      (node (ref "C40") (pin "2") (pinfunction "2_2") (pintype "passive"))
      (node (ref "C41") (pin "1") (pinfunction "1_1") (pintype "passive"))
      (node (ref "C60") (pin "2") (pinfunction "2_2") (pintype "passive"))
      (node (ref "Q1") (pin "D") (pinfunction "D_D") (pintype "passive"))
      (node (ref "Q2") (pin "D") (pinfunction "D_D") (pintype "passive"))
      (node (ref "Q3") (pin "D") (pinfunction "D_D") (pintype "passive"))
      (node (ref "Q4") (pin "D") (pinfunction "D_D") (pintype "passive"))
      (node (ref "Q5") (pin "D") (pinfunction "D_D") (pintype "passive"))
      (node (ref "Q6") (pin "D") (pinfunction "D_D") (pintype "passive"))
      (node (ref "U4") (pin "29") (pinfunction "PVDD1_29") (pintype "passive"))
      (node (ref "U4") (pin "53") (pinfunction "PVDD2_53") (pintype "passive"))
      (node (ref "U4") (pin "54") (pinfunction "PVDD2_54") (pintype "passive"))
    )
    (net (code "37") (name "GND") (class "Default")
      (node (ref "C24") (pin "2") (pinfunction "2_2") (pintype "passive"))
      (node (ref "C25") (pin "2") (pinfunction "2_2") (pintype "passive"))
      (node (ref "C27") (pin "2") (pinfunction "2_2") (pintype "passive"))
      (node (ref "C29") (pin "2") (pinfunction "2_2") (pintype "passive"))
      (node (ref "C32") (pin "1") (pinfunction "1_1") (pintype "passive"))
      (node (ref "C41") (pin "2") (pinfunction "2_2") (pintype "passive"))
      (node (ref "C60") (pin "1") (pinfunction "1_1") (pintype "passive"))
      (node (ref "D1") (pin "A") (pinfunction "A_A") (pintype "passive"))
      (node (ref "R15") (pin "2") (pinfunction "0_2") (pintype "passive"))
      (node (ref "R20") (pin "2") (pinfunction "0_2") (pintype "passive"))
      (node (ref "R21") (pin "2") (pinfunction "0_2") (pintype "passive"))
      (node (ref "U4") (pin "57") (pinfunction "GND_(PowerPAD)_57") (pintype "passive"))
    )
    (net (code "38") (name "GVDD") (class "Default")
      (node (ref "C32") (pin "2") (pinfunction "2_2") (pintype "passive"))
      (node (ref "U4") (pin "13") (pinfunction "GVDD_13") (pintype "passive"))
    )
    (net (code "39") (name "Net-(C27-Pad1)") (class "Default")
      (node (ref "C27") (pin "1") (pinfunction "1_1") (pintype "passive"))
      (node (ref "R14") (pin "2") (pinfunction "0_2") (pintype "passive"))
    )
    (net (code "40") (name "Net-(C28-Pad1)") (class "Default")
      (node (ref "C28") (pin "1") (pinfunction "1_1") (pintype "passive"))
      (node (ref "D1") (pin "K") (pinfunction "K_K") (pintype "passive"))
      (node (ref "L2") (pin "1") (pinfunction "1_1") (pintype "passive"))
      (node (ref "U4") (pin "50") (pinfunction "PH_50") (pintype "passive"))
      (node (ref "U4") (pin "51") (pinfunction "PH_51") (pintype "passive"))
    )
    (net (code "41") (name "Net-(Q1-PadG)") (class "Default")
      (node (ref "Q1") (pin "G") (pinfunction "G_G") (pintype "passive"))
      (node (ref "Q2") (pin "G") (pinfunction "G_G") (pintype "passive"))
      (node (ref "R17") (pin "1") (pinfunction "0_1") (pintype "passive"))
    )
    (net (code "42") (name "Net-(Q3-PadG)") (class "Default")
      (node (ref "Q3") (pin "G") (pinfunction "G_G") (pintype "passive"))
      (node (ref "Q4") (pin "G") (pinfunction "G_G") (pintype "passive"))
      (node (ref "R18") (pin "1") (pinfunction "0_1") (pintype "passive"))
    )
    (net (code "43") (name "Net-(Q5-PadG)") (class "Default")
      (node (ref "Q5") (pin "G") (pinfunction "G_G") (pintype "passive"))
      (node (ref "Q6") (pin "G") (pinfunction "G_G") (pintype "passive"))
      (node (ref "R19") (pin "1") (pinfunction "0_1") (pintype "passive"))
    )
    (net (code "44") (name "Net-(Q7-PadG)") (class "Default")
      (node (ref "Q7") (pin "G") (pinfunction "G_G") (pintype "passive"))
      (node (ref "Q8") (pin "G") (pinfunction "G_G") (pintype "passive"))
      (node (ref "R22") (pin "1") (pinfunction "0_1") (pintype "passive"))
    )
    (net (code "45") (name "Net-(Q10-PadG)") (class "Default")
      (node (ref "Q10") (pin "G") (pinfunction "G_G") (pintype "passive"))
      (node (ref "Q9") (pin "G") (pinfunction "G_G") (pintype "passive"))
      (node (ref "R23") (pin "1") (pinfunction "0_1") (pintype "passive"))
    )
    (net (code "46") (name "Net-(Q11-PadG)") (class "Default")
      (node (ref "Q11") (pin "G") (pinfunction "G_G") (pintype "passive"))
      (node (ref "Q12") (pin "G") (pinfunction "G_G") (pintype "passive"))
      (node (ref "R24") (pin "1") (pinfunction "0_1") (pintype "passive"))
    )
    (net (code "47") (name "Net-(U4-AVDD)") (class "Default")
      (node (ref "C37") (pin "2") (pinfunction "2_2") (pintype "passive"))
      (node (ref "U4") (pin "27") (pinfunction "AVDD_27") (pintype "passive"))
    )
    (net (code "48") (name "Net-(U4-BST_A)") (class "Default")
      (node (ref "C30") (pin "2") (pinfunction "2_2") (pintype "passive"))
      (node (ref "U4") (pin "48") (pinfunction "BST_A_48") (pintype "passive"))
    )
    (net (code "49") (name "Net-(U4-BST_B)") (class "Default")
      (node (ref "C31") (pin "2") (pinfunction "2_2") (pintype "passive"))
      (node (ref "U4") (pin "43") (pinfunction "BST_B_43") (pintype "passive"))
    )
    (net (code "50") (name "Net-(U4-BST_BK)") (class "Default")
      (node (ref "C28") (pin "2") (pinfunction "2_2") (pintype "passive"))
      (node (ref "U4") (pin "52") (pinfunction "BST_BK_52") (pintype "passive"))
    )
    (net (code "51") (name "Net-(U4-BST_C)") (class "Default")
      (node (ref "C34") (pin "2") (pinfunction "2_2") (pintype "passive"))
      (node (ref "U4") (pin "38") (pinfunction "BST_C_38") (pintype "passive"))
    )
    (net (code "52") (name "Net-(U4-COMP)") (class "Default")
      (node (ref "C24") (pin "1") (pinfunction "1_1") (pintype "passive"))
      (node (ref "R14") (pin "1") (pinfunction "0_1") (pintype "passive"))
      (node (ref "U4") (pin "2") (pinfunction "COMP_2") (pintype "passive"))
    )
    (net (code "53") (name "Net-(U4-CP1)") (class "Default")
      (node (ref "C33") (pin "1") (pinfunction "1_1") (pintype "passive"))
      (node (ref "U4") (pin "14") (pinfunction "CP1_14") (pintype "passive"))
    )
    (net (code "54") (name "Net-(U4-CP2)") (class "Default")
      (node (ref "C33") (pin "2") (pinfunction "2_2") (pintype "passive"))
      (node (ref "U4") (pin "15") (pinfunction "CP2_15") (pintype "passive"))
    )
    (net (code "55") (name "Net-(U4-DTC)") (class "Default")
      (node (ref "R21") (pin "1") (pinfunction "0_1") (pintype "passive"))
      (node (ref "U4") (pin "7") (pinfunction "DTC_7") (pintype "passive"))
    )
    (net (code "56") (name "Net-(U4-DVDD)") (class "Default")
      (node (ref "C35") (pin "2") (pinfunction "2_2") (pintype "passive"))
      (node (ref "U4") (pin "23") (pinfunction "DVDD_23") (pintype "passive"))
    )
    (net (code "57") (name "Net-(U4-RT_CLK)") (class "Default")
      (node (ref "R15") (pin "1") (pinfunction "0_1") (pintype "passive"))
      (node (ref "U4") (pin "1") (pinfunction "RT_CLK_1") (pintype "passive"))
    )
    (net (code "58") (name "Net-(U4-SN1)") (class "Default")
      (node (ref "C36") (pin "1") (pinfunction "1_1") (pintype "passive"))
      (node (ref "R25") (pin "2") (pinfunction "0_2") (pintype "passive"))
      (node (ref "U4") (pin "33") (pinfunction "SN1_33") (pintype "passive"))
    )
    (net (code "59") (name "Net-(U4-SN2)") (class "Default")
      (node (ref "C42") (pin "1") (pinfunction "1_1") (pintype "passive"))
      (node (ref "R30") (pin "2") (pinfunction "0_2") (pintype "passive"))
      (node (ref "U4") (pin "31") (pinfunction "SN2_31") (pintype "passive"))
    )
    (net (code "60") (name "Net-(U4-SO1)") (class "Default")
      (node (ref "R26") (pin "1") (pinfunction "0_1") (pintype "passive"))
      (node (ref "U4") (pin "25") (pinfunction "SO1_25") (pintype "passive"))
    )
    (net (code "61") (name "Net-(U4-SO2)") (class "Default")
      (node (ref "R29") (pin "1") (pinfunction "0_1") (pintype "passive"))
      (node (ref "U4") (pin "26") (pinfunction "SO2_26") (pintype "passive"))
    )
    (net (code "62") (name "Net-(U4-VSENSE)") (class "Default")
      (node (ref "R16") (pin "2") (pinfunction "0_2") (pintype "passive"))
      (node (ref "R20") (pin "1") (pinfunction "0_1") (pintype "passive"))
      (node (ref "U4") (pin "3") (pinfunction "VSENSE_3") (pintype "passive"))
    )
    (net (code "63") (name "PGND") (class "Default")
      (node (ref "C26") (pin "1") (pinfunction "1_1") (pintype "passive"))
      (node (ref "C40") (pin "1") (pinfunction "1_1") (pintype "passive"))
      (node (ref "NT2") (pin "2") (pintype "passive"))
      (node (ref "NT3") (pin "2") (pintype "passive"))
      (node (ref "Q7") (pin "S") (pinfunction "S_S") (pintype "passive"))
      (node (ref "Q8") (pin "S") (pinfunction "S_S") (pintype "passive"))
      (node (ref "R27") (pin "1") (pinfunction "0_1") (pintype "passive"))
      (node (ref "R28") (pin "1") (pinfunction "0_1") (pintype "passive"))
      (node (ref "U4") (pin "44") (pinfunction "SL_A_44") (pintype "passive"))
    )
    (net (code "64") (name "VCC") (class "Default")
      (node (ref "U4") (pin "49") (pinfunction "VDD_SPI_49") (pintype "passive"))
    )
    (net (code "65") (name "unconnected-(U4-EN_BUCK-Pad55)") (class "Default")
      (node (ref "U4") (pin "55") (pinfunction "EN_BUCK_55") (pintype "passive"))
    )
    (net (code "66") (name "unconnected-(U4-PWRGD-Pad4)") (class "Default")
      (node (ref "U4") (pin "4") (pinfunction "PWRGD_4") (pintype "passive"))
    )
    (net (code "67") (name "unconnected-(U4-SS_TR-Pad56)") (class "Default")
      (node (ref "U4") (pin "56") (pinfunction "SS_TR_56") (pintype "passive"))
    )
  )
)
